# Debug.net
KiCad netlist of a schematic drawn in Altium Designer
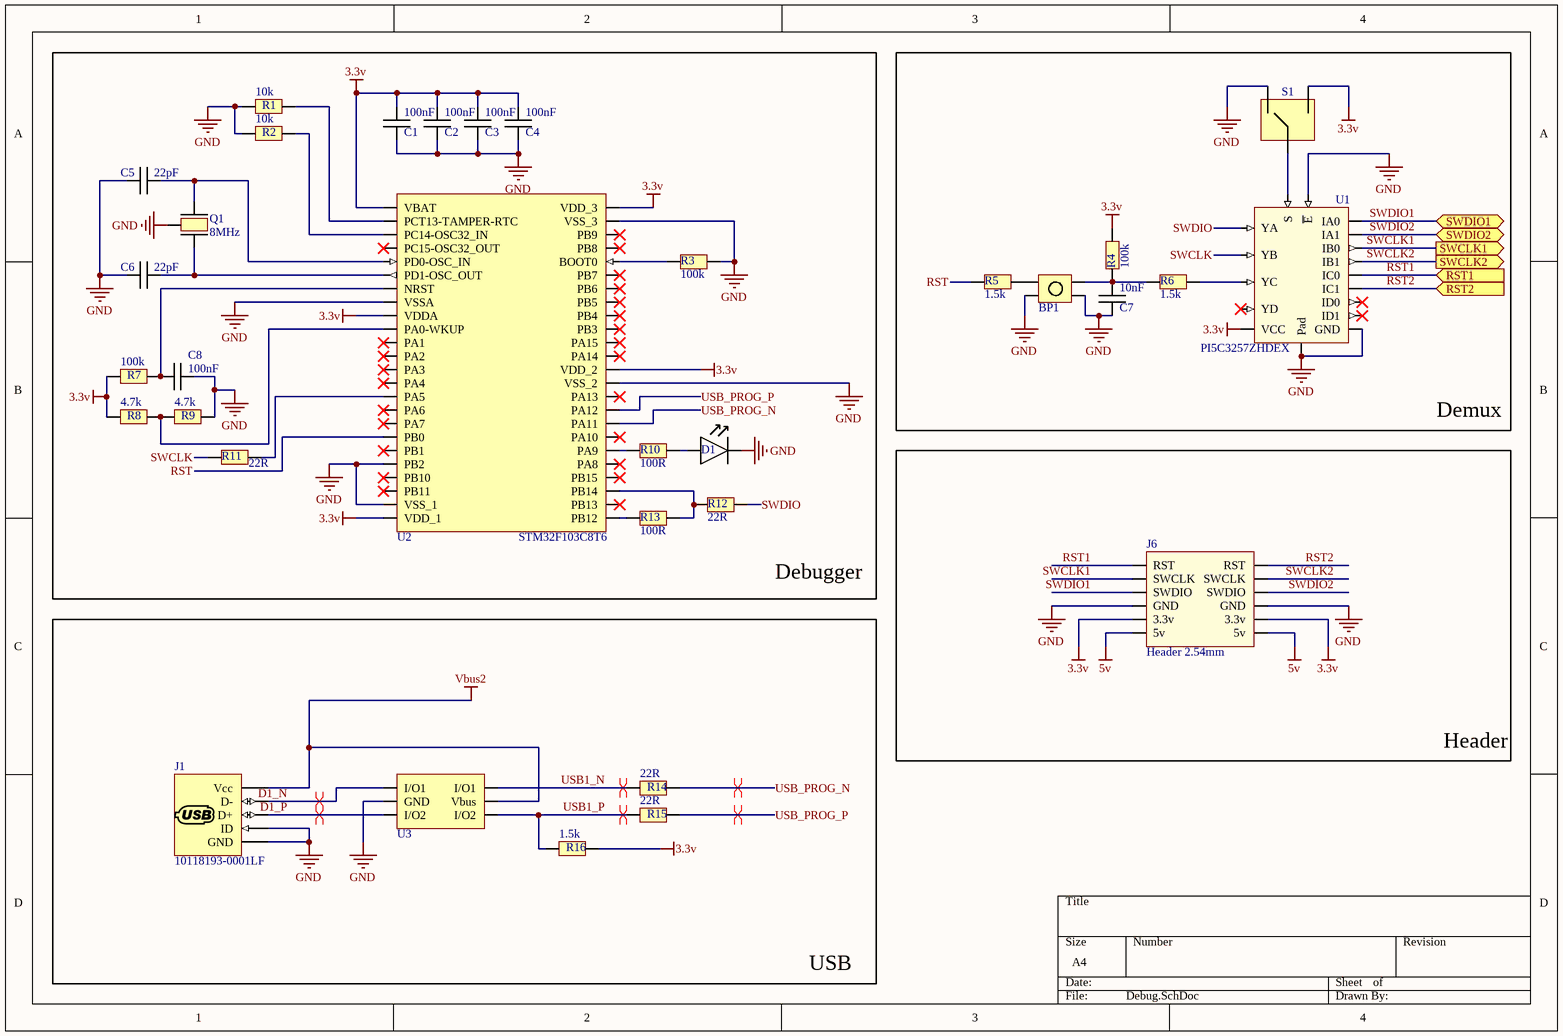
[diagram p0: Debug.SchDoc]

(export (version "E")
  (design (tool "Eeschema 10.0.6"))
  (components
    (comp (ref "BP1") (value "BP") (footprint "BP") (libsource (lib "Carte_design_SCHLib") (part "BP")))
    (comp (ref "C1") (value "100nF") (footprint "0603") (libsource (lib "Carte_design_SCHLib") (part "Capa")))
    (comp (ref "C2") (value "100nF") (footprint "0603") (libsource (lib "Carte_design_SCHLib") (part "Capa")))
    (comp (ref "C3") (value "100nF") (footprint "0603") (libsource (lib "Carte_design_SCHLib") (part "Capa")))
    (comp (ref "C4") (value "100nF") (footprint "0603") (libsource (lib "Carte_design_SCHLib") (part "Capa")))
    (comp (ref "C5") (value "22pF") (footprint "0603") (libsource (lib "Carte_design_SCHLib") (part "Capa")))
    (comp (ref "C6") (value "22pF") (footprint "0603") (libsource (lib "Carte_design_SCHLib") (part "Capa")))
    (comp (ref "C7") (value "10nF") (footprint "0603") (libsource (lib "Carte_design_SCHLib") (part "Capa")))
    (comp (ref "C8") (value "100nF") (footprint "0603") (libsource (lib "Carte_design_SCHLib") (part "Capa")))
    (comp (ref "D1")
      (value "Led")
      (footprint "LED_0603")
      (libsource (lib "Carte_design_SCHLib") (part "Led"))
    )
    (comp (ref "J1")
      (value "10118193-0001LF")
      (footprint "Mini_USB_mixte")
      (description "CONN RCPT USB2.0 MICRO B SMD R/A")
      (libsource (lib "Carte_design_SCHLib") (part "10118193-0001LF"))
    )
    (comp (ref "J6")
      (value "Header 2.54mm")
      (footprint "Header_prog")
      (libsource (lib "Carte_design_SCHLib") (part "Header_prog"))
    )
    (comp (ref "Q1")
      (value "8MHz")
      (footprint "Quartz_prog")
      (fields (field (name "TOLERANCE") "20ppm"))
      (libsource (lib "Carte_design_SCHLib") (part "Quartz_8MHz"))
    )
    (comp (ref "R1") (value "10k") (footprint "0603") (libsource (lib "") (part "Resistance_1")))
    (comp (ref "R2") (value "10k") (footprint "0603") (libsource (lib "") (part "Resistance_1")))
    (comp (ref "R3") (value "100k") (footprint "0603") (libsource (lib "") (part "Resistance_1")))
    (comp (ref "R4") (value "100k") (footprint "0603") (libsource (lib "") (part "Resistance_2")))
    (comp (ref "R5")
      (value "1.5k")
      (footprint "0603")
      (libsource (lib "Carte_design_SCHLib") (part "Resistance"))
    )
    (comp (ref "R6")
      (value "1.5k")
      (footprint "0603")
      (libsource (lib "Carte_design_SCHLib") (part "Resistance"))
    )
    (comp (ref "R7") (value "100k") (footprint "0603") (libsource (lib "") (part "Resistance_1")))
    (comp (ref "R8") (value "4.7k") (footprint "0603") (libsource (lib "") (part "Resistance_1")))
    (comp (ref "R9") (value "4.7k") (footprint "0603") (libsource (lib "") (part "Resistance_1")))
    (comp (ref "R10") (value "100R") (footprint "0603") (libsource (lib "") (part "Resistance_1")))
    (comp (ref "R11") (value "22R") (footprint "0603") (libsource (lib "") (part "Resistance_1")))
    (comp (ref "R12") (value "22R") (footprint "0603") (libsource (lib "") (part "Resistance_1")))
    (comp (ref "R13") (value "100R") (footprint "0603") (libsource (lib "") (part "Resistance_1")))
    (comp (ref "R14") (value "22R") (footprint "0603") (libsource (lib "") (part "Resistance_1")))
    (comp (ref "R15") (value "22R") (footprint "0603") (libsource (lib "") (part "Resistance_1")))
    (comp (ref "R16") (value "1.5k") (footprint "0603") (libsource (lib "") (part "Resistance_1")))
    (comp (ref "S1")
      (value "microswitch")
      (footprint "Switch_slider")
      (libsource (lib "Carte_design_SCHLib") (part "microswitch"))
    )
    (comp (ref "U1")
      (value "PI5C3257ZHDEX")
      (footprint "QFN50P300X300X65_HS-17M")
      (description "Multiplexer/Demultiplexer Bus Switch 4-Channel 2: 1 16-Pin UQFN T/R")
      (libsource (lib "Carte_design_SCHLib") (part "PI5C3257ZHDEX"))
    )
    (comp (ref "U2")
      (value "STM32F103C8T6")
      (footprint "CQFP50P900X900X160-48M")
      (libsource (lib "Carte_design_SCHLib") (part "STM32F103C8T6"))
    )
    (comp (ref "U3")
      (value "USBLC6-2P6")
      (footprint "SOT95P280X145-6M")
      (description "TVS DIODE 5.25V 17V SOT666")
      (libsource (lib "Carte_design_SCHLib") (part "USBLC6-2P6"))
    )
  )
  (nets
    (net (code "1") (name "/D1_N") (class "Default")
      (node (ref "J1") (pin "2") (pinfunction "D-_2") (pintype "bidirectional"))
      (node (ref "U3") (pin "1") (pinfunction "I/O1_1") (pintype "passive"))
    )
    (net (code "2") (name "/D1_P") (class "Default")
      (node (ref "J1") (pin "3") (pinfunction "D+_3") (pintype "bidirectional"))
      (node (ref "U3") (pin "3") (pinfunction "I/O2_3") (pintype "passive"))
    )
    (net (code "3") (name "/RST") (class "Default")
      (node (ref "R5") (pin "2") (pinfunction "27_2") (pintype "passive"))
      (node (ref "U2") (pin "18") (pinfunction "PB0_18") (pintype "bidirectional"))
    )
    (net (code "4") (name "/RST1") (class "Default")
      (node (ref "J6") (pin "1") (pinfunction "RST_1") (pintype "passive"))
      (node (ref "U1") (pin "11") (pinfunction "IC0_11") (pintype "bidirectional"))
    )
    (net (code "5") (name "/RST2") (class "Default")
      (node (ref "J6") (pin "12") (pinfunction "RST_12") (pintype "passive"))
      (node (ref "U1") (pin "10") (pinfunction "IC1_10") (pintype "bidirectional"))
    )
    (net (code "6") (name "/SWCLK") (class "Default")
      (node (ref "R11") (pin "1") (pinfunction "26_1") (pintype "passive"))
      (node (ref "U1") (pin "7") (pinfunction "YB_7") (pintype "input"))
    )
    (net (code "7") (name "/SWCLK1") (class "Default")
      (node (ref "J6") (pin "2") (pinfunction "SWCLK_2") (pintype "passive"))
      (node (ref "U1") (pin "5") (pinfunction "IB0_5") (pintype "output"))
    )
    (net (code "8") (name "/SWCLK2") (class "Default")
      (node (ref "J6") (pin "11") (pinfunction "SWCLK_11") (pintype "passive"))
      (node (ref "U1") (pin "6") (pinfunction "IB1_6") (pintype "output"))
    )
    (net (code "9") (name "/SWDIO") (class "Default")
      (node (ref "R12") (pin "2") (pinfunction "27_2") (pintype "passive"))
      (node (ref "U1") (pin "4") (pinfunction "YA_4") (pintype "input"))
    )
    (net (code "10") (name "/SWDIO1") (class "Default")
      (node (ref "J6") (pin "3") (pinfunction "SWDIO_3") (pintype "passive"))
      (node (ref "U1") (pin "2") (pinfunction "IA0_2") (pintype "bidirectional"))
    )
    (net (code "11") (name "/SWDIO2") (class "Default")
      (node (ref "J6") (pin "10") (pinfunction "SWDIO_10") (pintype "passive"))
      (node (ref "U1") (pin "3") (pinfunction "IA1_3") (pintype "bidirectional"))
    )
    (net (code "12") (name "/USB1_N") (class "Default")
      (node (ref "R14") (pin "1") (pinfunction "26_1") (pintype "passive"))
      (node (ref "U3") (pin "6") (pinfunction "I/O1_6") (pintype "passive"))
    )
    (net (code "13") (name "/USB1_P") (class "Default")
      (node (ref "R15") (pin "1") (pinfunction "26_1") (pintype "passive"))
      (node (ref "R16") (pin "1") (pinfunction "26_1") (pintype "passive"))
      (node (ref "U3") (pin "4") (pinfunction "I/O2_4") (pintype "passive"))
    )
    (net (code "14") (name "/USB_PROG_N") (class "Default")
      (node (ref "R14") (pin "2") (pinfunction "27_2") (pintype "passive"))
      (node (ref "U2") (pin "32") (pinfunction "PA11_32") (pintype "bidirectional"))
    )
    (net (code "15") (name "/USB_PROG_P") (class "Default")
      (node (ref "R15") (pin "2") (pinfunction "27_2") (pintype "passive"))
      (node (ref "U2") (pin "33") (pinfunction "PA12_33") (pintype "bidirectional"))
    )
    (net (code "16") (name "3.3v") (class "Default")
      (node (ref "C1") (pin "2") (pinfunction "28_2") (pintype "passive"))
      (node (ref "C2") (pin "2") (pinfunction "28_2") (pintype "passive"))
      (node (ref "C3") (pin "2") (pinfunction "28_2") (pintype "passive"))
      (node (ref "C4") (pin "2") (pinfunction "28_2") (pintype "passive"))
      (node (ref "J6") (pin "5") (pinfunction "3.3v_5") (pintype "passive"))
      (node (ref "J6") (pin "8") (pinfunction "3.3v_8") (pintype "passive"))
      (node (ref "R16") (pin "2") (pinfunction "27_2") (pintype "passive"))
      (node (ref "R4") (pin "2") (pinfunction "27_2") (pintype "passive"))
      (node (ref "R7") (pin "1") (pinfunction "26_1") (pintype "passive"))
      (node (ref "R8") (pin "1") (pinfunction "26_1") (pintype "passive"))
      (node (ref "S1") (pin "1") (pinfunction "NO7_1") (pintype "passive"))
      (node (ref "U1") (pin "16") (pinfunction "VCC_16") (pintype "power_in"))
      (node (ref "U2") (pin "1") (pinfunction "VBAT_1") (pintype "power_in"))
      (node (ref "U2") (pin "24") (pinfunction "VDD_1_24") (pintype "power_in"))
      (node (ref "U2") (pin "36") (pinfunction "VDD_2_36") (pintype "power_in"))
      (node (ref "U2") (pin "48") (pinfunction "VDD_3_48") (pintype "power_in"))
      (node (ref "U2") (pin "9") (pinfunction "VDDA_9") (pintype "power_in"))
    )
    (net (code "17") (name "5v") (class "Default")
      (node (ref "J6") (pin "6") (pinfunction "5v_6") (pintype "passive"))
      (node (ref "J6") (pin "7") (pinfunction "5v_7") (pintype "passive"))
    )
    (net (code "18") (name "GND") (class "Default")
      (node (ref "BP1") (pin "2") (pinfunction "S_2") (pintype "passive"))
      (node (ref "BP1") (pin "3") (pinfunction "S_3") (pintype "passive"))
      (node (ref "C1") (pin "1") (pinfunction "29_1") (pintype "passive"))
      (node (ref "C2") (pin "1") (pinfunction "29_1") (pintype "passive"))
      (node (ref "C3") (pin "1") (pinfunction "29_1") (pintype "passive"))
      (node (ref "C4") (pin "1") (pinfunction "29_1") (pintype "passive"))
      (node (ref "C5") (pin "1") (pinfunction "29_1") (pintype "passive"))
      (node (ref "C6") (pin "1") (pinfunction "29_1") (pintype "passive"))
      (node (ref "C7") (pin "1") (pinfunction "29_1") (pintype "passive"))
      (node (ref "C8") (pin "2") (pinfunction "28_2") (pintype "passive"))
      (node (ref "D1") (pin "2") (pinfunction "31_2") (pintype "passive"))
      (node (ref "J1") (pin "4") (pinfunction "ID_4") (pintype "input"))
      (node (ref "J1") (pin "5") (pinfunction "GND_5") (pintype "power_in"))
      (node (ref "J6") (pin "4") (pinfunction "GND_4") (pintype "passive"))
      (node (ref "J6") (pin "9") (pinfunction "GND_9") (pintype "passive"))
      (node (ref "Q1") (pin "3") (pinfunction "3_3") (pintype "passive"))
      (node (ref "R1") (pin "1") (pinfunction "26_1") (pintype "passive"))
      (node (ref "R2") (pin "1") (pinfunction "26_1") (pintype "passive"))
      (node (ref "R3") (pin "2") (pinfunction "27_2") (pintype "passive"))
      (node (ref "R9") (pin "2") (pinfunction "27_2") (pintype "passive"))
      (node (ref "S1") (pin "3") (pinfunction "NO6_3") (pintype "passive"))
      (node (ref "U1") (pin "15") (pinfunction "~{E}_15") (pintype "input"))
      (node (ref "U1") (pin "17") (pinfunction "Pad_17") (pintype "power_in"))
      (node (ref "U1") (pin "8") (pinfunction "GND_8") (pintype "power_in"))
      (node (ref "U2") (pin "20") (pinfunction "PB2_20") (pintype "bidirectional"))
      (node (ref "U2") (pin "23") (pinfunction "VSS_1_23") (pintype "power_in"))
      (node (ref "U2") (pin "35") (pinfunction "VSS_2_35") (pintype "power_in"))
      (node (ref "U2") (pin "47") (pinfunction "VSS_3_47") (pintype "power_in"))
      (node (ref "U2") (pin "8") (pinfunction "VSSA_8") (pintype "power_in"))
      (node (ref "U3") (pin "2") (pinfunction "GND_2") (pintype "passive"))
    )
    (net (code "19") (name "Net-(C5-28)") (class "Default")
      (node (ref "C5") (pin "2") (pinfunction "28_2") (pintype "passive"))
      (node (ref "Q1") (pin "1") (pinfunction "15_1") (pintype "passive"))
      (node (ref "U2") (pin "5") (pinfunction "PD0-OSC_IN_5") (pintype "input"))
    )
    (net (code "20") (name "Net-(C6-28)") (class "Default")
      (node (ref "C6") (pin "2") (pinfunction "28_2") (pintype "passive"))
      (node (ref "Q1") (pin "2") (pinfunction "16_2") (pintype "passive"))
      (node (ref "U2") (pin "6") (pinfunction "PD1-OSC_OUT_6") (pintype "output"))
    )
    (net (code "21") (name "Net-(C7-28)") (class "Default")
      (node (ref "BP1") (pin "4") (pinfunction "S_4") (pintype "passive"))
      (node (ref "C7") (pin "2") (pinfunction "28_2") (pintype "passive"))
      (node (ref "R4") (pin "1") (pinfunction "26_1") (pintype "passive"))
      (node (ref "R6") (pin "2") (pinfunction "27_2") (pintype "passive"))
    )
    (net (code "22") (name "Net-(C8-29)") (class "Default")
      (node (ref "C8") (pin "1") (pinfunction "29_1") (pintype "passive"))
      (node (ref "R7") (pin "2") (pinfunction "27_2") (pintype "passive"))
      (node (ref "U2") (pin "7") (pinfunction "NRST_7") (pintype "bidirectional"))
    )
    (net (code "23") (name "Net-(D1-30)") (class "Default")
      (node (ref "D1") (pin "1") (pinfunction "30_1") (pintype "passive"))
      (node (ref "R10") (pin "2") (pinfunction "27_2") (pintype "passive"))
    )
    (net (code "24") (name "Net-(R1-27)") (class "Default")
      (node (ref "R1") (pin "2") (pinfunction "27_2") (pintype "passive"))
      (node (ref "U2") (pin "2") (pinfunction "PCT13-TAMPER-RTC_2") (pintype "bidirectional"))
    )
    (net (code "25") (name "Net-(R2-27)") (class "Default")
      (node (ref "R2") (pin "2") (pinfunction "27_2") (pintype "passive"))
      (node (ref "U2") (pin "3") (pinfunction "PC14-OSC32_IN_3") (pintype "bidirectional"))
    )
    (net (code "26") (name "Net-(R3-26)") (class "Default")
      (node (ref "R3") (pin "1") (pinfunction "26_1") (pintype "passive"))
      (node (ref "U2") (pin "44") (pinfunction "BOOT0_44") (pintype "input"))
    )
    (net (code "27") (name "Net-(R5-26)") (class "Default")
      (node (ref "BP1") (pin "1") (pinfunction "S_1") (pintype "passive"))
      (node (ref "R5") (pin "1") (pinfunction "26_1") (pintype "passive"))
    )
    (net (code "28") (name "Net-(R6-26)") (class "Default")
      (node (ref "R6") (pin "1") (pinfunction "26_1") (pintype "passive"))
      (node (ref "U1") (pin "9") (pinfunction "YC_9") (pintype "input"))
    )
    (net (code "29") (name "Net-(R8-27)") (class "Default")
      (node (ref "R8") (pin "2") (pinfunction "27_2") (pintype "passive"))
      (node (ref "R9") (pin "1") (pinfunction "26_1") (pintype "passive"))
      (node (ref "U2") (pin "10") (pinfunction "PA0-WKUP_10") (pintype "bidirectional"))
    )
    (net (code "30") (name "Net-(R10-26)") (class "Default")
      (node (ref "R10") (pin "1") (pinfunction "26_1") (pintype "passive"))
      (node (ref "U2") (pin "30") (pinfunction "PA9_30") (pintype "bidirectional"))
    )
    (net (code "31") (name "Net-(R11-27)") (class "Default")
      (node (ref "R11") (pin "2") (pinfunction "27_2") (pintype "passive"))
      (node (ref "U2") (pin "15") (pinfunction "PA5_15") (pintype "bidirectional"))
    )
    (net (code "32") (name "Net-(R12-26)") (class "Default")
      (node (ref "R12") (pin "1") (pinfunction "26_1") (pintype "passive"))
      (node (ref "R13") (pin "2") (pinfunction "27_2") (pintype "passive"))
      (node (ref "U2") (pin "27") (pinfunction "PB14_27") (pintype "bidirectional"))
    )
    (net (code "33") (name "Net-(R13-26)") (class "Default")
      (node (ref "R13") (pin "1") (pinfunction "26_1") (pintype "passive"))
      (node (ref "U2") (pin "25") (pinfunction "PB12_25") (pintype "bidirectional"))
    )
    (net (code "34") (name "Net-(S1-NO5)") (class "Default")
      (node (ref "S1") (pin "2") (pinfunction "NO5_2") (pintype "passive"))
      (node (ref "U1") (pin "1") (pinfunction "S_1") (pintype "input"))
    )
    (net (code "35") (name "Vbus2") (class "Default")
      (node (ref "J1") (pin "1") (pinfunction "Vcc_1") (pintype "power_in"))
      (node (ref "U3") (pin "5") (pinfunction "Vbus_5") (pintype "passive"))
    )
    (net (code "36") (name "unconnected-(U1-ID0-Pad14)") (class "Default")
      (node (ref "U1") (pin "14") (pinfunction "ID0_14") (pintype "output+no_connect"))
    )
    (net (code "37") (name "unconnected-(U1-ID1-Pad13)") (class "Default")
      (node (ref "U1") (pin "13") (pinfunction "ID1_13") (pintype "output+no_connect"))
    )
    (net (code "38") (name "unconnected-(U1-YD-Pad12)") (class "Default")
      (node (ref "U1") (pin "12") (pinfunction "YD_12") (pintype "input+no_connect"))
    )
    (net (code "39") (name "unconnected-(U2-PA1-Pad11)") (class "Default")
      (node (ref "U2") (pin "11") (pinfunction "PA1_11") (pintype "bidirectional+no_connect"))
    )
    (net (code "40") (name "unconnected-(U2-PA2-Pad12)") (class "Default")
      (node (ref "U2") (pin "12") (pinfunction "PA2_12") (pintype "bidirectional+no_connect"))
    )
    (net (code "41") (name "unconnected-(U2-PA3-Pad13)") (class "Default")
      (node (ref "U2") (pin "13") (pinfunction "PA3_13") (pintype "bidirectional+no_connect"))
    )
    (net (code "42") (name "unconnected-(U2-PA4-Pad14)") (class "Default")
      (node (ref "U2") (pin "14") (pinfunction "PA4_14") (pintype "bidirectional+no_connect"))
    )
    (net (code "43") (name "unconnected-(U2-PA6-Pad16)") (class "Default")
      (node (ref "U2") (pin "16") (pinfunction "PA6_16") (pintype "bidirectional+no_connect"))
    )
    (net (code "44") (name "unconnected-(U2-PA7-Pad17)") (class "Default")
      (node (ref "U2") (pin "17") (pinfunction "PA7_17") (pintype "bidirectional+no_connect"))
    )
    (net (code "45") (name "unconnected-(U2-PA8-Pad29)") (class "Default")
      (node (ref "U2") (pin "29") (pinfunction "PA8_29") (pintype "bidirectional+no_connect"))
    )
    (net (code "46") (name "unconnected-(U2-PA10-Pad31)") (class "Default")
      (node (ref "U2") (pin "31") (pinfunction "PA10_31") (pintype "bidirectional+no_connect"))
    )
    (net (code "47") (name "unconnected-(U2-PA13-Pad34)") (class "Default")
      (node (ref "U2") (pin "34") (pinfunction "PA13_34") (pintype "bidirectional+no_connect"))
    )
    (net (code "48") (name "unconnected-(U2-PA14-Pad37)") (class "Default")
      (node (ref "U2") (pin "37") (pinfunction "PA14_37") (pintype "bidirectional+no_connect"))
    )
    (net (code "49") (name "unconnected-(U2-PA15-Pad38)") (class "Default")
      (node (ref "U2") (pin "38") (pinfunction "PA15_38") (pintype "bidirectional+no_connect"))
    )
    (net (code "50") (name "unconnected-(U2-PB1-Pad19)") (class "Default")
      (node (ref "U2") (pin "19") (pinfunction "PB1_19") (pintype "bidirectional+no_connect"))
    )
    (net (code "51") (name "unconnected-(U2-PB3-Pad39)") (class "Default")
      (node (ref "U2") (pin "39") (pinfunction "PB3_39") (pintype "bidirectional+no_connect"))
    )
    (net (code "52") (name "unconnected-(U2-PB4-Pad40)") (class "Default")
      (node (ref "U2") (pin "40") (pinfunction "PB4_40") (pintype "bidirectional+no_connect"))
    )
    (net (code "53") (name "unconnected-(U2-PB5-Pad41)") (class "Default")
      (node (ref "U2") (pin "41") (pinfunction "PB5_41") (pintype "bidirectional+no_connect"))
    )
    (net (code "54") (name "unconnected-(U2-PB6-Pad42)") (class "Default")
      (node (ref "U2") (pin "42") (pinfunction "PB6_42") (pintype "bidirectional+no_connect"))
    )
    (net (code "55") (name "unconnected-(U2-PB7-Pad43)") (class "Default")
      (node (ref "U2") (pin "43") (pinfunction "PB7_43") (pintype "bidirectional+no_connect"))
    )
    (net (code "56") (name "unconnected-(U2-PB8-Pad45)") (class "Default")
      (node (ref "U2") (pin "45") (pinfunction "PB8_45") (pintype "bidirectional+no_connect"))
    )
    (net (code "57") (name "unconnected-(U2-PB9-Pad46)") (class "Default")
      (node (ref "U2") (pin "46") (pinfunction "PB9_46") (pintype "bidirectional+no_connect"))
    )
    (net (code "58") (name "unconnected-(U2-PB10-Pad21)") (class "Default")
      (node (ref "U2") (pin "21") (pinfunction "PB10_21") (pintype "bidirectional+no_connect"))
    )
    (net (code "59") (name "unconnected-(U2-PB11-Pad22)") (class "Default")
      (node (ref "U2") (pin "22") (pinfunction "PB11_22") (pintype "bidirectional+no_connect"))
    )
    (net (code "60") (name "unconnected-(U2-PB13-Pad26)") (class "Default")
      (node (ref "U2") (pin "26") (pinfunction "PB13_26") (pintype "bidirectional+no_connect"))
    )
    (net (code "61") (name "unconnected-(U2-PB15-Pad28)") (class "Default")
      (node (ref "U2") (pin "28") (pinfunction "PB15_28") (pintype "bidirectional+no_connect"))
    )
    (net (code "62") (name "unconnected-(U2-PC15-OSC32_OUT-Pad4)") (class "Default")
      (node (ref "U2") (pin "4") (pinfunction "PC15-OSC32_OUT_4") (pintype "bidirectional+no_connect"))
    )
  )
)
